# Tayloe_Detector.net
KiCad netlist of a schematic drawn in EAGLE
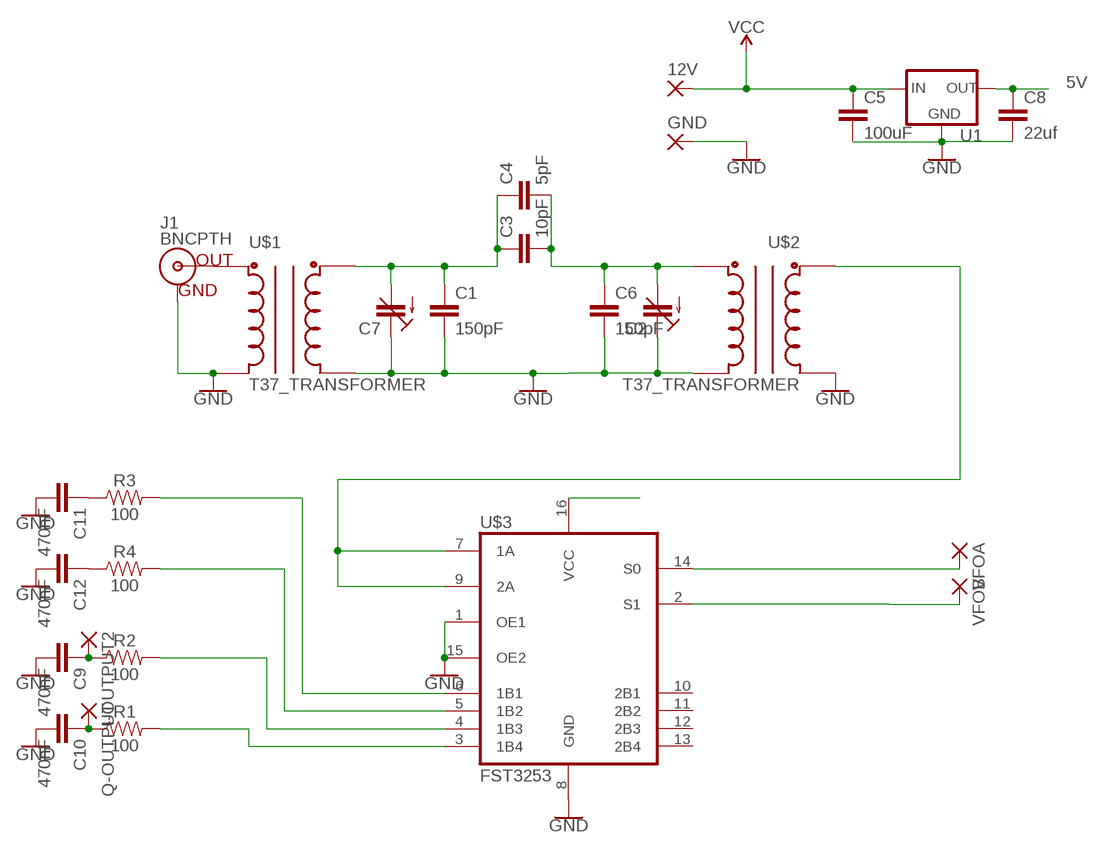
[diagram p0: schematic, sheet 1]

(export (version "E")
  (design (tool "Eeschema 10.0.6"))
  (components
    (comp (ref "12V")
      (value "3,17/1,1")
      (footprint "eagle-import:3,17_1,1")
      (libsource (lib "eagle-import") (part "3,17/1,1"))
    )
    (comp (ref "C1")
      (value "150pF")
      (footprint "eagle-import:C5B3.5")
      (libsource (lib "eagle-import") (part "C5/3.5"))
    )
    (comp (ref "C2")
      (value "C-TRIMMTZ03")
      (footprint "eagle-import:CTRIMTZ03")
      (libsource (lib "eagle-import") (part "C-TRIMMTZ03"))
    )
    (comp (ref "C3")
      (value "10pF")
      (footprint "eagle-import:C5B3.5")
      (libsource (lib "eagle-import") (part "C5/3.5"))
    )
    (comp (ref "C4")
      (value "5pF")
      (footprint "eagle-import:C5B3.5")
      (libsource (lib "eagle-import") (part "C5/3.5"))
    )
    (comp (ref "C5")
      (value "100uF")
      (footprint "eagle-import:C5B3.5")
      (libsource (lib "eagle-import") (part "C5/3.5"))
    )
    (comp (ref "C6")
      (value "150pF")
      (footprint "eagle-import:C5B3.5")
      (libsource (lib "eagle-import") (part "C5/3.5"))
    )
    (comp (ref "C7")
      (value "C-TRIMMTZ03")
      (footprint "eagle-import:CTRIMTZ03")
      (libsource (lib "eagle-import") (part "C-TRIMMTZ03"))
    )
    (comp (ref "C8")
      (value "22uf")
      (footprint "eagle-import:C5B3.5")
      (libsource (lib "eagle-import") (part "C5/3.5"))
    )
    (comp (ref "C9")
      (value "470nF")
      (footprint "eagle-import:C5B3.5")
      (libsource (lib "eagle-import") (part "C5/3.5"))
    )
    (comp (ref "C10")
      (value "470nF")
      (footprint "eagle-import:C5B3.5")
      (libsource (lib "eagle-import") (part "C5/3.5"))
    )
    (comp (ref "C11")
      (value "470nF")
      (footprint "eagle-import:C5B3.5")
      (libsource (lib "eagle-import") (part "C5/3.5"))
    )
    (comp (ref "C12")
      (value "470nF")
      (footprint "eagle-import:C5B3.5")
      (libsource (lib "eagle-import") (part "C5/3.5"))
    )
    (comp (ref "GND")
      (value "3,17/1,1")
      (footprint "eagle-import:3,17_1,1")
      (libsource (lib "eagle-import") (part "3,17/1,1"))
    )
    (comp (ref "I-OUTPUT2")
      (value "3,17/1,1")
      (footprint "eagle-import:3,17_1,1")
      (libsource (lib "eagle-import") (part "3,17/1,1"))
    )
    (comp (ref "J1")
      (value "BNCPTH")
      (footprint "eagle-import:BNC")
      (libsource (lib "eagle-import") (part "BNCPTH"))
    )
    (comp (ref "Q-OUTPUT")
      (value "3,17/1,1")
      (footprint "eagle-import:3,17_1,1")
      (libsource (lib "eagle-import") (part "3,17/1,1"))
    )
    (comp (ref "R1")
      (value "100")
      (footprint "eagle-import:AXIAL-0.3")
      (libsource (lib "eagle-import") (part "1KOHM-HORIZ-1/4W-1%"))
    )
    (comp (ref "R2")
      (value "100")
      (footprint "eagle-import:AXIAL-0.3")
      (libsource (lib "eagle-import") (part "1KOHM-HORIZ-1/4W-1%"))
    )
    (comp (ref "R3")
      (value "100")
      (footprint "eagle-import:AXIAL-0.3")
      (libsource (lib "eagle-import") (part "1KOHM-HORIZ-1/4W-1%"))
    )
    (comp (ref "R4")
      (value "100")
      (footprint "eagle-import:AXIAL-0.3")
      (libsource (lib "eagle-import") (part "1KOHM-HORIZ-1/4W-1%"))
    )
    (comp (ref "U$1")
      (value "T37_TRANSFORMER")
      (footprint "eagle-import:T37_TRANSFORMER")
      (libsource (lib "eagle-import") (part "T37_TRANSFORMER"))
    )
    (comp (ref "U$2")
      (value "T37_TRANSFORMER")
      (footprint "eagle-import:T37_TRANSFORMER")
      (libsource (lib "eagle-import") (part "T37_TRANSFORMER"))
    )
    (comp (ref "U$3")
      (value "FST3253")
      (footprint "eagle-import:SO16")
      (libsource (lib "eagle-import") (part "FST3253"))
    )
    (comp (ref "U1")
      (value "V_REG_78XXTO-92_UNTESTED")
      (footprint "eagle-import:TO-92")
      (libsource (lib "eagle-import") (part "V_REG_78XXTO-92_UNTESTED"))
    )
    (comp (ref "VFOA")
      (value "3,17/1,1")
      (footprint "eagle-import:3,17_1,1")
      (libsource (lib "eagle-import") (part "3,17/1,1"))
    )
    (comp (ref "VFOB")
      (value "3,17/1,1")
      (footprint "eagle-import:3,17_1,1")
      (libsource (lib "eagle-import") (part "3,17/1,1"))
    )
  )
  (nets
    (net (code "1") (name "/5V") (class "Default")
      (node (ref "C8") (pin "1") (pinfunction "1_1") (pintype "passive"))
      (node (ref "U$3") (pin "16") (pinfunction "VCC_16") (pintype "bidirectional"))
      (node (ref "U1") (pin "1") (pinfunction "OUT_1") (pintype "passive"))
    )
    (net (code "2") (name "GND") (class "Default")
      (node (ref "C1") (pin "2") (pinfunction "2_2") (pintype "passive"))
      (node (ref "C10") (pin "2") (pinfunction "2_2") (pintype "passive"))
      (node (ref "C11") (pin "2") (pinfunction "2_2") (pintype "passive"))
      (node (ref "C12") (pin "2") (pinfunction "2_2") (pintype "passive"))
      (node (ref "C2") (pin "1") (pinfunction "E_1") (pintype "passive"))
      (node (ref "C5") (pin "2") (pinfunction "2_2") (pintype "passive"))
      (node (ref "C6") (pin "2") (pinfunction "2_2") (pintype "passive"))
      (node (ref "C7") (pin "1") (pinfunction "E_1") (pintype "passive"))
      (node (ref "C8") (pin "2") (pinfunction "2_2") (pintype "passive"))
      (node (ref "C9") (pin "2") (pinfunction "2_2") (pintype "passive"))
      (node (ref "GND") (pin "1") (pinfunction "P_1") (pintype "passive"))
      (node (ref "J1") (pin "GND") (pinfunction "GND_GND") (pintype "bidirectional"))
      (node (ref "U$1") (pin "C1A") (pinfunction "C1A_C1A") (pintype "bidirectional"))
      (node (ref "U$1") (pin "C2A") (pinfunction "C2A_C2A") (pintype "bidirectional"))
      (node (ref "U$2") (pin "C1A") (pinfunction "C1A_C1A") (pintype "bidirectional"))
      (node (ref "U$2") (pin "C2A") (pinfunction "C2A_C2A") (pintype "bidirectional"))
      (node (ref "U$3") (pin "1") (pinfunction "OE1_1") (pintype "bidirectional"))
      (node (ref "U$3") (pin "15") (pinfunction "OE2_15") (pintype "bidirectional"))
      (node (ref "U$3") (pin "8") (pinfunction "GND_8") (pintype "bidirectional"))
      (node (ref "U1") (pin "2") (pinfunction "GND_2") (pintype "input"))
    )
    (net (code "3") (name "Net-(C2-A)") (class "Default")
      (node (ref "C2") (pin "2") (pinfunction "A_2") (pintype "passive"))
      (node (ref "C3") (pin "2") (pinfunction "2_2") (pintype "passive"))
      (node (ref "C4") (pin "2") (pinfunction "2_2") (pintype "passive"))
      (node (ref "C6") (pin "1") (pinfunction "1_1") (pintype "passive"))
      (node (ref "U$2") (pin "C2B") (pinfunction "C2B_C2B") (pintype "bidirectional"))
    )
    (net (code "4") (name "Net-(C7-A)") (class "Default")
      (node (ref "C1") (pin "1") (pinfunction "1_1") (pintype "passive"))
      (node (ref "C3") (pin "1") (pinfunction "1_1") (pintype "passive"))
      (node (ref "C4") (pin "1") (pinfunction "1_1") (pintype "passive"))
      (node (ref "C7") (pin "2") (pinfunction "A_2") (pintype "passive"))
      (node (ref "U$1") (pin "C2B") (pinfunction "C2B_C2B") (pintype "bidirectional"))
    )
    (net (code "5") (name "Net-(I-OUTPUT2-P)") (class "Default")
      (node (ref "C9") (pin "1") (pinfunction "1_1") (pintype "passive"))
      (node (ref "I-OUTPUT2") (pin "1") (pinfunction "P_1") (pintype "passive"))
      (node (ref "R2") (pin "P$1") (pinfunction "1_P$1") (pintype "passive"))
    )
    (net (code "6") (name "Net-(J1-OUT)") (class "Default")
      (node (ref "J1") (pin "S") (pinfunction "OUT_S") (pintype "bidirectional"))
      (node (ref "U$1") (pin "C1B") (pinfunction "C1B_C1B") (pintype "bidirectional"))
    )
    (net (code "7") (name "Net-(Q-OUTPUT-P)") (class "Default")
      (node (ref "C10") (pin "1") (pinfunction "1_1") (pintype "passive"))
      (node (ref "Q-OUTPUT") (pin "1") (pinfunction "P_1") (pintype "passive"))
      (node (ref "R1") (pin "P$1") (pinfunction "1_P$1") (pintype "passive"))
    )
    (net (code "8") (name "Net-(R1-2)") (class "Default")
      (node (ref "R1") (pin "P$2") (pinfunction "2_P$2") (pintype "passive"))
      (node (ref "U$3") (pin "3") (pinfunction "1B4_3") (pintype "output"))
    )
    (net (code "9") (name "Net-(R2-2)") (class "Default")
      (node (ref "R2") (pin "P$2") (pinfunction "2_P$2") (pintype "passive"))
      (node (ref "U$3") (pin "4") (pinfunction "1B3_4") (pintype "output"))
    )
    (net (code "10") (name "Net-(R3-1)") (class "Default")
      (node (ref "C11") (pin "1") (pinfunction "1_1") (pintype "passive"))
      (node (ref "R3") (pin "P$1") (pinfunction "1_P$1") (pintype "passive"))
    )
    (net (code "11") (name "Net-(R3-2)") (class "Default")
      (node (ref "R3") (pin "P$2") (pinfunction "2_P$2") (pintype "passive"))
      (node (ref "U$3") (pin "6") (pinfunction "1B1_6") (pintype "input"))
    )
    (net (code "12") (name "Net-(R4-1)") (class "Default")
      (node (ref "C12") (pin "1") (pinfunction "1_1") (pintype "passive"))
      (node (ref "R4") (pin "P$1") (pinfunction "1_P$1") (pintype "passive"))
    )
    (net (code "13") (name "Net-(R4-2)") (class "Default")
      (node (ref "R4") (pin "P$2") (pinfunction "2_P$2") (pintype "passive"))
      (node (ref "U$3") (pin "5") (pinfunction "1B2_5") (pintype "input"))
    )
    (net (code "14") (name "Net-(U$3-1A)") (class "Default")
      (node (ref "U$2") (pin "C1B") (pinfunction "C1B_C1B") (pintype "bidirectional"))
      (node (ref "U$3") (pin "7") (pinfunction "1A_7") (pintype "bidirectional"))
      (node (ref "U$3") (pin "9") (pinfunction "2A_9") (pintype "bidirectional"))
    )
    (net (code "15") (name "Net-(U$3-S0)") (class "Default")
      (node (ref "U$3") (pin "14") (pinfunction "S0_14") (pintype "bidirectional"))
      (node (ref "VFOA") (pin "1") (pinfunction "P_1") (pintype "passive"))
    )
    (net (code "16") (name "Net-(U$3-S1)") (class "Default")
      (node (ref "U$3") (pin "2") (pinfunction "S1_2") (pintype "bidirectional"))
      (node (ref "VFOB") (pin "1") (pinfunction "P_1") (pintype "passive"))
    )
    (net (code "17") (name "VCC") (class "Default")
      (node (ref "12V") (pin "1") (pinfunction "P_1") (pintype "passive"))
      (node (ref "C5") (pin "1") (pinfunction "1_1") (pintype "passive"))
      (node (ref "U1") (pin "3") (pinfunction "IN_3") (pintype "input"))
    )
    (net (code "18") (name "unconnected-(U$3-2B1-Pad10)") (class "Default")
      (node (ref "U$3") (pin "10") (pinfunction "2B1_10") (pintype "output"))
    )
    (net (code "19") (name "unconnected-(U$3-2B2-Pad11)") (class "Default")
      (node (ref "U$3") (pin "11") (pinfunction "2B2_11") (pintype "output"))
    )
    (net (code "20") (name "unconnected-(U$3-2B3-Pad12)") (class "Default")
      (node (ref "U$3") (pin "12") (pinfunction "2B3_12") (pintype "input"))
    )
    (net (code "21") (name "unconnected-(U$3-2B4-Pad13)") (class "Default")
      (node (ref "U$3") (pin "13") (pinfunction "2B4_13") (pintype "input"))
    )
  )
)
